# main.net
KiCad netlist of a schematic drawn in Altium Designer
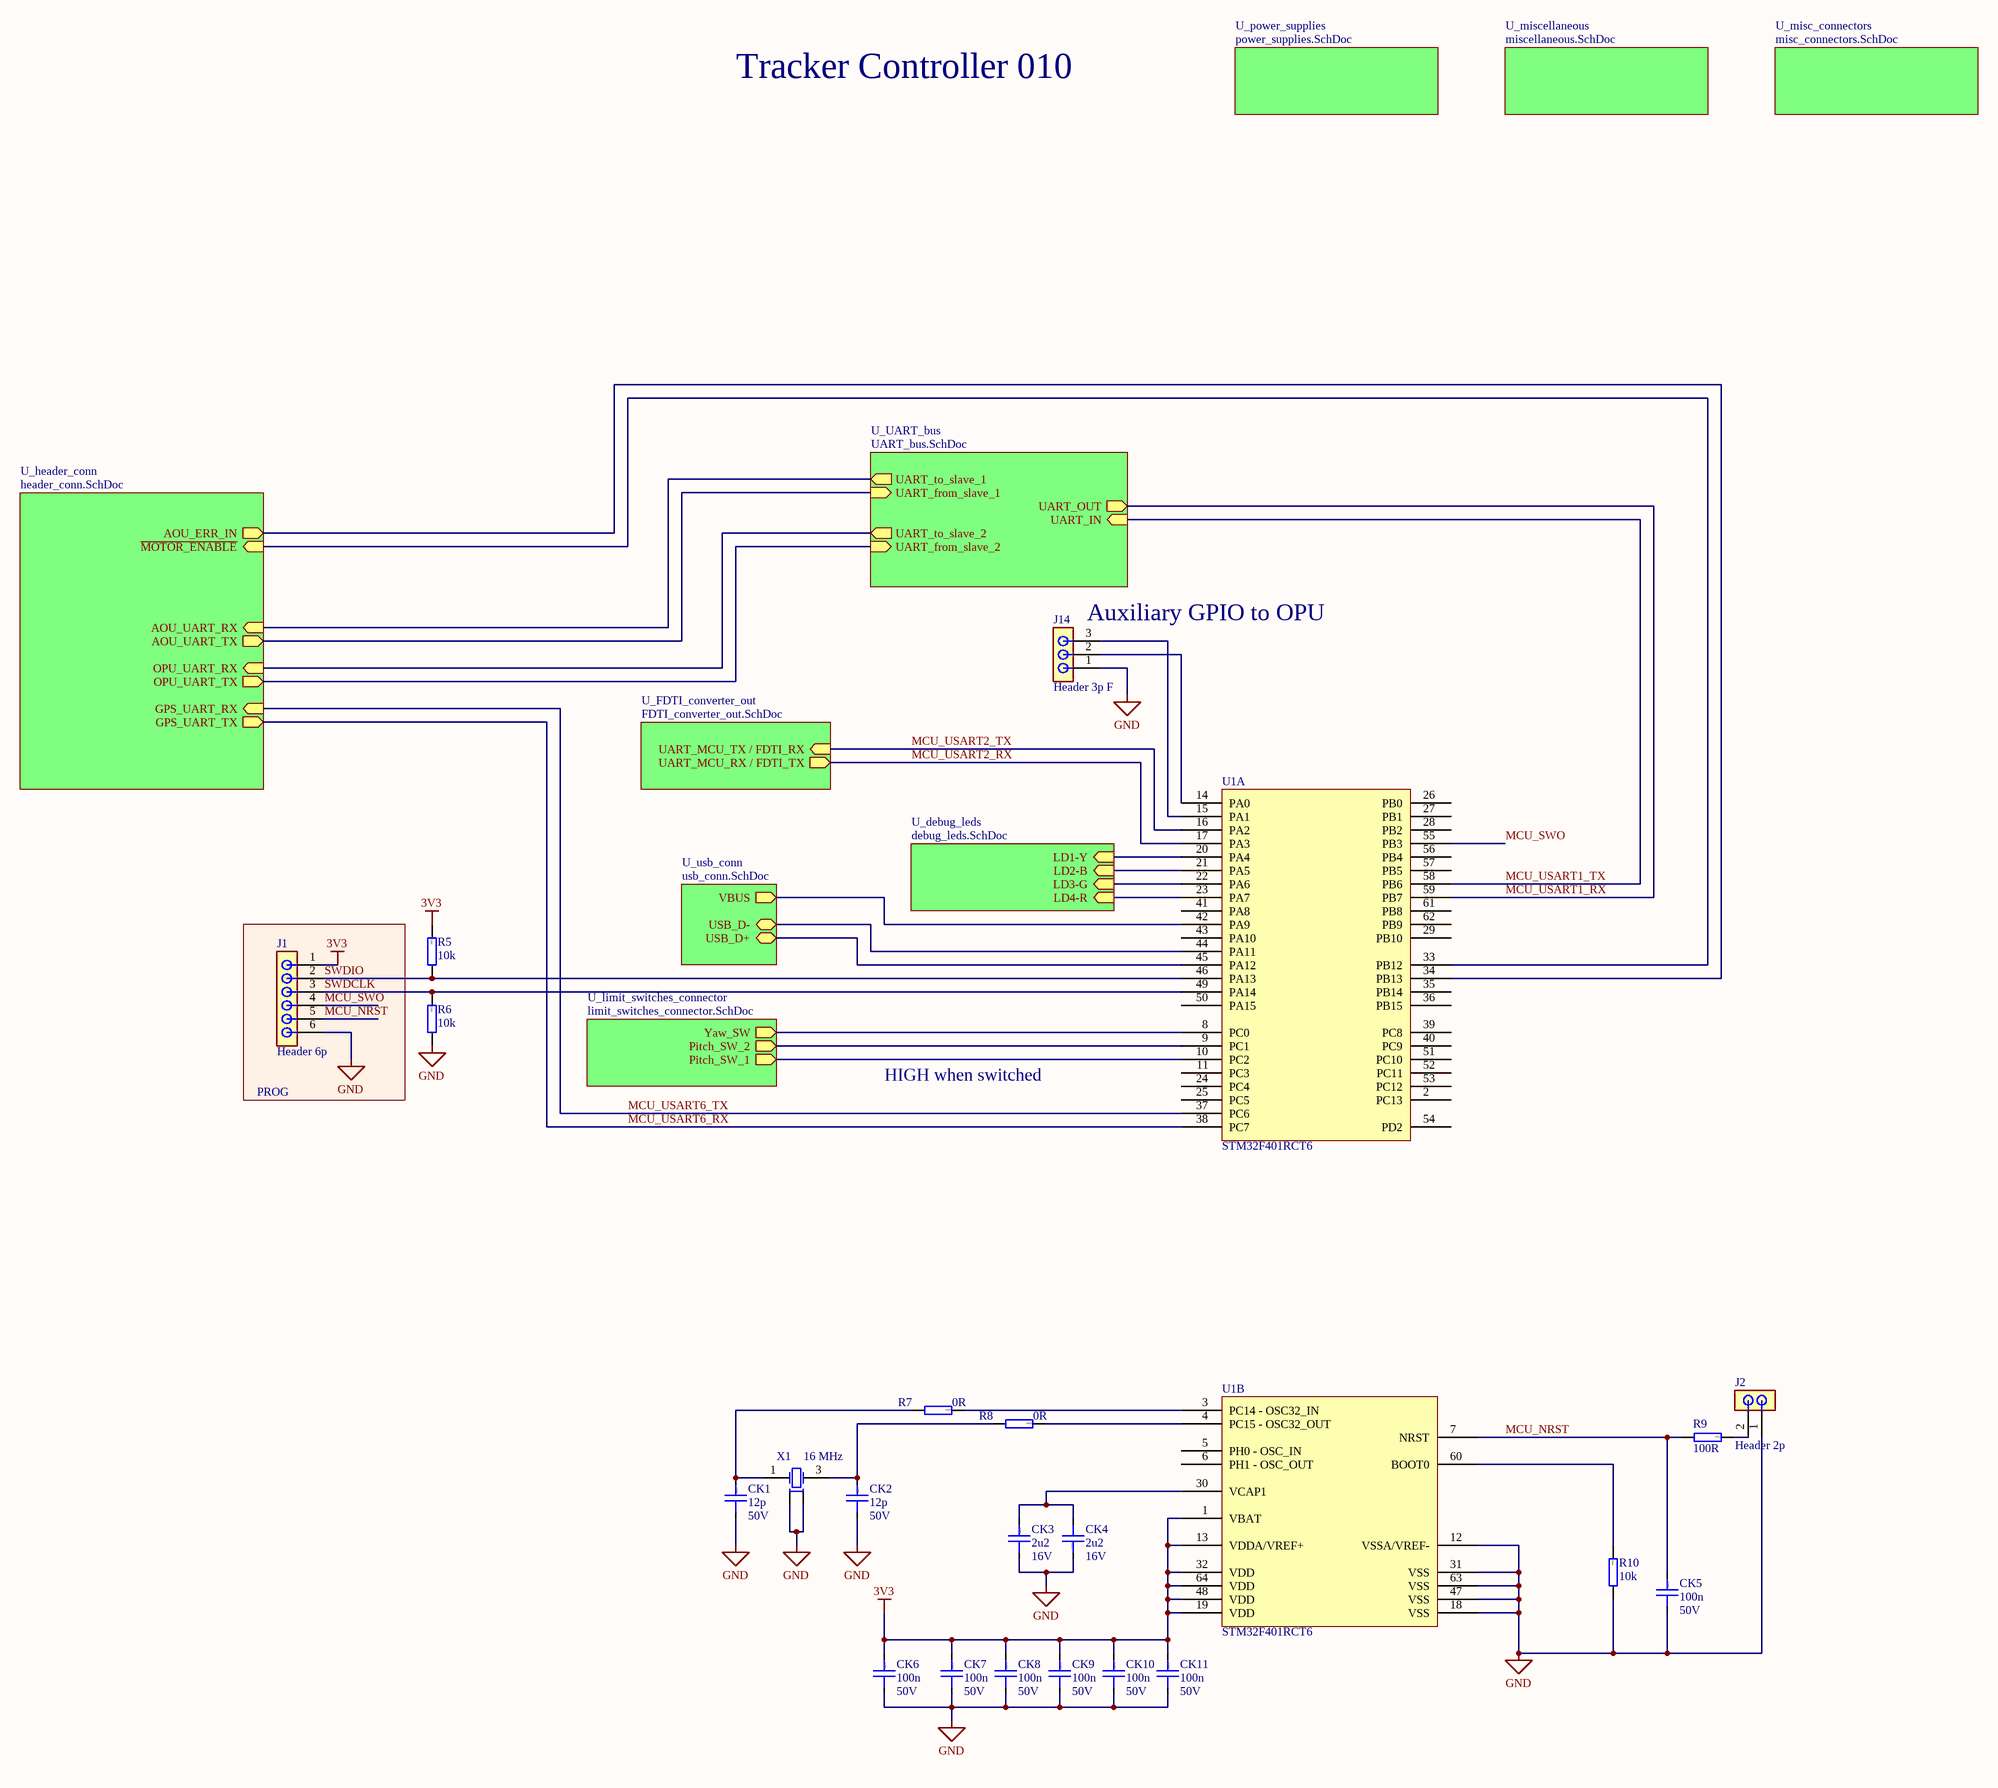
[diagram p0: main.SchDoc]

(export (version "E")
  (design (tool "Eeschema 10.0.6"))
  (components
    (comp (ref "CK1")
      (value "12p")
      (footprint "CAP0603")
      (description "50V 12pF C0G ±5% 0603 Multilayer Ceramic Capacitors MLCC - SMD/SMT ROHS")
      (fields (field (name "JLCPCB PART") "C38523") (field (name "VOLTAGE RATING") "50V"))
      (libsource (lib "Kubikova ultra knihovna") (part "Cap 12p 0603"))
    )
    (comp (ref "CK2")
      (value "12p")
      (footprint "CAP0603")
      (description "50V 12pF C0G ±5% 0603 Multilayer Ceramic Capacitors MLCC - SMD/SMT ROHS")
      (fields (field (name "JLCPCB PART") "C38523") (field (name "VOLTAGE RATING") "50V"))
      (libsource (lib "Kubikova ultra knihovna") (part "Cap 12p 0603"))
    )
    (comp (ref "CK3")
      (value "2u2")
      (footprint "CAP0603")
      (description "16V 2.2uF X5R ±10% 0603 Multilayer Ceramic Capacitors MLCC - SMD/SMT ROHS")
      (fields (field (name "JLCPCB PART") "C23630") (field (name "VOLTAGE RATING") "16V"))
      (libsource (lib "Kubikova ultra knihovna") (part "Cap 2u2 0603"))
    )
    (comp (ref "CK4")
      (value "2u2")
      (footprint "CAP0603")
      (description "16V 2.2uF X5R ±10% 0603 Multilayer Ceramic Capacitors MLCC - SMD/SMT ROHS")
      (fields (field (name "JLCPCB PART") "C23630") (field (name "VOLTAGE RATING") "16V"))
      (libsource (lib "Kubikova ultra knihovna") (part "Cap 2u2 0603"))
    )
    (comp (ref "CK5")
      (value "100n")
      (footprint "CAP0603")
      (description "50V 100nF X7R ±10% 0603 Multilayer Ceramic Capacitors MLCC - SMD/SMT ROHS")
      (fields (field (name "JLCPCB PART") "C14663") (field (name "VOLTAGE RATING") "50V"))
      (libsource (lib "Kubikova ultra knihovna") (part "Cap 100n 0603"))
    )
    (comp (ref "CK6")
      (value "100n")
      (footprint "CAP0603")
      (description "50V 100nF X7R ±10% 0603 Multilayer Ceramic Capacitors MLCC - SMD/SMT ROHS")
      (fields (field (name "JLCPCB PART") "C14663") (field (name "VOLTAGE RATING") "50V"))
      (libsource (lib "Kubikova ultra knihovna") (part "Cap 100n 0603"))
    )
    (comp (ref "CK7")
      (value "100n")
      (footprint "CAP0603")
      (description "50V 100nF X7R ±10% 0603 Multilayer Ceramic Capacitors MLCC - SMD/SMT ROHS")
      (fields (field (name "JLCPCB PART") "C14663") (field (name "VOLTAGE RATING") "50V"))
      (libsource (lib "Kubikova ultra knihovna") (part "Cap 100n 0603"))
    )
    (comp (ref "CK8")
      (value "100n")
      (footprint "CAP0603")
      (description "50V 100nF X7R ±10% 0603 Multilayer Ceramic Capacitors MLCC - SMD/SMT ROHS")
      (fields (field (name "JLCPCB PART") "C14663") (field (name "VOLTAGE RATING") "50V"))
      (libsource (lib "Kubikova ultra knihovna") (part "Cap 100n 0603"))
    )
    (comp (ref "CK9")
      (value "100n")
      (footprint "CAP0603")
      (description "50V 100nF X7R ±10% 0603 Multilayer Ceramic Capacitors MLCC - SMD/SMT ROHS")
      (fields (field (name "JLCPCB PART") "C14663") (field (name "VOLTAGE RATING") "50V"))
      (libsource (lib "Kubikova ultra knihovna") (part "Cap 100n 0603"))
    )
    (comp (ref "CK10")
      (value "100n")
      (footprint "CAP0603")
      (description "50V 100nF X7R ±10% 0603 Multilayer Ceramic Capacitors MLCC - SMD/SMT ROHS")
      (fields (field (name "JLCPCB PART") "C14663") (field (name "VOLTAGE RATING") "50V"))
      (libsource (lib "Kubikova ultra knihovna") (part "Cap 100n 0603"))
    )
    (comp (ref "CK11")
      (value "100n")
      (footprint "CAP0603")
      (description "50V 100nF X7R ±10% 0603 Multilayer Ceramic Capacitors MLCC - SMD/SMT ROHS")
      (fields (field (name "JLCPCB PART") "C14663") (field (name "VOLTAGE RATING") "50V"))
      (libsource (lib "Kubikova ultra knihovna") (part "Cap 100n 0603"))
    )
    (comp (ref "J1")
      (value "Header 6p")
      (footprint "Pin header 6p")
      (fields
        (field (name "MANUFACTURER_PART_NUMBER") "DS1021-1*2SF11-B")
        (field (name "JLCPCB PART") "C37208")
      )
      (libsource (lib "Kubikova ultra knihovna") (part "Pin header 6p"))
    )
    (comp (ref "J2")
      (value "Header 2p")
      (footprint "Pin header 2p")
      (description "Connector")
      (fields
        (field (name "MANUFACTURER_PART_NUMBER") "DS1021-1*2SF11-B")
        (field (name "JLCPCB PART") "C492401")
      )
      (libsource (lib "Kubikova ultra knihovna") (part "Pin header 2p"))
    )
    (comp (ref "J14")
      (value "Header 3p F")
      (footprint "Pin header 3p - F")
      (description "Direct Insert 2.54mm Policy 3A 2.5mm -40℃~+105℃ 3mm 6mm 250V Black 1x3P Single Row 3P Pin Headers")
      (fields (field (name "MANUFACTURER_PART_NUMBER") "DS1021-1*2SF11-B"))
      (libsource (lib "Kubikova ultra knihovna") (part "Pin header 3p_F"))
    )
    (comp (ref "R5")
      (value "10k")
      (footprint "RESC2012X06N(SMR0805)")
      (description "125mW Thick Film Resistors 150V ±100ppm/℃ ±1% 10kΩ 0805 Chip Resistor - Surface Mount ROHS")
      (fields (field (name "JLCPCB PART") "C17414"))
      (libsource (lib "Kubikova ultra knihovna") (part "Res 10k 0805"))
    )
    (comp (ref "R6")
      (value "10k")
      (footprint "RESC2012X06N(SMR0805)")
      (description "125mW Thick Film Resistors 150V ±100ppm/℃ ±1% 10kΩ 0805 Chip Resistor - Surface Mount ROHS")
      (fields (field (name "JLCPCB PART") "C17414"))
      (libsource (lib "Kubikova ultra knihovna") (part "Res 10k 0805"))
    )
    (comp (ref "R7")
      (value "0R")
      (footprint "RESC2012X06N(SMR0805)")
      (description "125mW Thick Film Resistors 150V ±800ppm/℃ ±1% 0Ω 0805 Chip Resistor - Surface Mount ROHS")
      (fields (field (name "JLCPCB PART") "C17477") (field (name "AUTHOR") "JP/27.03.2014"))
      (libsource (lib "Kubikova ultra knihovna") (part "Res 0R 0805"))
    )
    (comp (ref "R8")
      (value "0R")
      (footprint "RESC2012X06N(SMR0805)")
      (description "125mW Thick Film Resistors 150V ±800ppm/℃ ±1% 0Ω 0805 Chip Resistor - Surface Mount ROHS")
      (fields (field (name "JLCPCB PART") "C17477") (field (name "AUTHOR") "JP/27.03.2014"))
      (libsource (lib "Kubikova ultra knihovna") (part "Res 0R 0805"))
    )
    (comp (ref "R9")
      (value "100R")
      (footprint "RESC2012X06N(SMR0805)")
      (description "125mW Thick Film Resistors 150V ±100ppm/℃ ±1% 100Ω 0805 Chip Resistor - Surface Mount ROHS")
      (fields (field (name "JLCPCB PART") "C17408") (field (name "AUTHOR") "JP/27.03.2014"))
      (libsource (lib "Kubikova ultra knihovna") (part "Res 100R 0805"))
    )
    (comp (ref "R10")
      (value "10k")
      (footprint "RESC2012X06N(SMR0805)")
      (description "125mW Thick Film Resistors 150V ±100ppm/℃ ±1% 10kΩ 0805 Chip Resistor - Surface Mount ROHS")
      (fields (field (name "JLCPCB PART") "C17414"))
      (libsource (lib "Kubikova ultra knihovna") (part "Res 10k 0805"))
    )
    (comp (ref "U1")
      (value "STM32F401RCT6")
      (footprint "LQFP64")
      (description "256KB 1.7V~3.6V ARM-M4 64KB 84MHz FLASH 50 LQFP-64(10x10) Microcontrollers (MCU/MPU/SOC) ROHS")
      (fields (field (name "JLCPCB PART") "C74524"))
      (libsource (lib "Kubikova ultra knihovna") (part "STM32F401RCT6"))
    )
    (comp (ref "X1")
      (value "16 MHz")
      (footprint "3225 XTal")
      (description "X322516MLB4SI\r\n16MHz Surface Mount Crystal 9pF ±10ppm ±20ppm SMD3225-4P Crystals ROHS")
      (libsource (lib "Kubikova ultra knihovna") (part "16 MHz crystal"))
    )
  )
  (nets
    (net (code "1") (name "/AOU_ERR_IN") (class "Default")
      (node (ref "U1") (pin "34") (pinfunction "PB13_34") (pintype "passive"))
    )
    (net (code "3") (name "/LD1-Y") (class "Default")
      (node (ref "U1") (pin "20") (pinfunction "PA4_20") (pintype "passive"))
    )
    (net (code "4") (name "/LD2-B") (class "Default")
      (node (ref "U1") (pin "21") (pinfunction "PA5_21") (pintype "passive"))
    )
    (net (code "5") (name "/LD3-G") (class "Default")
      (node (ref "U1") (pin "22") (pinfunction "PA6_22") (pintype "passive"))
    )
    (net (code "6") (name "/LD4-R") (class "Default")
      (node (ref "U1") (pin "23") (pinfunction "PA7_23") (pintype "passive"))
    )
    (net (code "7") (name "/MCU_NRST") (class "Default")
      (node (ref "CK5") (pin "1") (pinfunction "1_1") (pintype "passive"))
      (node (ref "J1") (pin "5") (pinfunction "5_5") (pintype "passive"))
      (node (ref "R9") (pin "1") (pinfunction "1_1") (pintype "passive"))
      (node (ref "U1") (pin "7") (pinfunction "NRST_7") (pintype "passive"))
    )
    (net (code "8") (name "/MCU_SWO") (class "Default")
      (node (ref "J1") (pin "4") (pinfunction "4_4") (pintype "passive"))
      (node (ref "U1") (pin "55") (pinfunction "PB3_55") (pintype "passive"))
    )
    (net (code "9") (name "/MCU_USART1_RX") (class "Default")
      (node (ref "U1") (pin "59") (pinfunction "PB7_59") (pintype "passive"))
    )
    (net (code "10") (name "/MCU_USART1_TX") (class "Default")
      (node (ref "U1") (pin "58") (pinfunction "PB6_58") (pintype "passive"))
    )
    (net (code "11") (name "/MCU_USART2_RX") (class "Default")
      (node (ref "U1") (pin "17") (pinfunction "PA3_17") (pintype "passive"))
    )
    (net (code "12") (name "/MCU_USART2_TX") (class "Default")
      (node (ref "U1") (pin "16") (pinfunction "PA2_16") (pintype "passive"))
    )
    (net (code "13") (name "/MCU_USART6_RX") (class "Default")
      (node (ref "U1") (pin "38") (pinfunction "PC7_38") (pintype "passive"))
    )
    (net (code "14") (name "/MCU_USART6_TX") (class "Default")
      (node (ref "U1") (pin "37") (pinfunction "PC6_37") (pintype "passive"))
    )
    (net (code "16") (name "/Pitch_SW_1") (class "Default")
      (node (ref "U1") (pin "10") (pinfunction "PC2_10") (pintype "passive"))
    )
    (net (code "17") (name "/Pitch_SW_2") (class "Default")
      (node (ref "U1") (pin "9") (pinfunction "PC1_9") (pintype "passive"))
    )
    (net (code "18") (name "/SWDCLK") (class "Default")
      (node (ref "J1") (pin "3") (pinfunction "3_3") (pintype "passive"))
      (node (ref "R6") (pin "2") (pinfunction "2_2") (pintype "passive"))
      (node (ref "U1") (pin "49") (pinfunction "PA14_49") (pintype "passive"))
    )
    (net (code "19") (name "/SWDIO") (class "Default")
      (node (ref "J1") (pin "2") (pinfunction "2_2") (pintype "passive"))
      (node (ref "R5") (pin "1") (pinfunction "1_1") (pintype "passive"))
      (node (ref "U1") (pin "46") (pinfunction "PA13_46") (pintype "passive"))
    )
    (net (code "22") (name "/USB_D+") (class "Default")
      (node (ref "U1") (pin "45") (pinfunction "PA12_45") (pintype "passive"))
    )
    (net (code "23") (name "/USB_D-") (class "Default")
      (node (ref "U1") (pin "44") (pinfunction "PA11_44") (pintype "passive"))
    )
    (net (code "24") (name "/VBUS") (class "Default")
      (node (ref "U1") (pin "42") (pinfunction "PA9_42") (pintype "passive"))
    )
    (net (code "25") (name "/Yaw_SW") (class "Default")
      (node (ref "U1") (pin "8") (pinfunction "PC0_8") (pintype "passive"))
    )
    (net (code "26") (name "/~{MOTOR_ENABLE}") (class "Default")
      (node (ref "U1") (pin "33") (pinfunction "PB12_33") (pintype "passive"))
    )
    (net (code "27") (name "3V3") (class "Default")
      (node (ref "CK10") (pin "1") (pinfunction "1_1") (pintype "passive"))
      (node (ref "CK11") (pin "1") (pinfunction "1_1") (pintype "passive"))
      (node (ref "CK6") (pin "1") (pinfunction "1_1") (pintype "passive"))
      (node (ref "CK7") (pin "1") (pinfunction "1_1") (pintype "passive"))
      (node (ref "CK8") (pin "1") (pinfunction "1_1") (pintype "passive"))
      (node (ref "CK9") (pin "1") (pinfunction "1_1") (pintype "passive"))
      (node (ref "J1") (pin "1") (pinfunction "1_1") (pintype "passive"))
      (node (ref "R5") (pin "2") (pinfunction "2_2") (pintype "passive"))
      (node (ref "U1") (pin "1") (pinfunction "VBAT_1") (pintype "passive"))
      (node (ref "U1") (pin "13") (pinfunction "VDDA/VREF+_13") (pintype "passive"))
      (node (ref "U1") (pin "19") (pinfunction "VDD_19") (pintype "passive"))
      (node (ref "U1") (pin "32") (pinfunction "VDD_32") (pintype "passive"))
      (node (ref "U1") (pin "48") (pinfunction "VDD_48") (pintype "passive"))
      (node (ref "U1") (pin "64") (pinfunction "VDD_64") (pintype "passive"))
    )
    (net (code "28") (name "GND") (class "Default")
      (node (ref "CK1") (pin "2") (pinfunction "2_2") (pintype "passive"))
      (node (ref "CK10") (pin "2") (pinfunction "2_2") (pintype "passive"))
      (node (ref "CK11") (pin "2") (pinfunction "2_2") (pintype "passive"))
      (node (ref "CK2") (pin "2") (pinfunction "2_2") (pintype "passive"))
      (node (ref "CK3") (pin "2") (pinfunction "2_2") (pintype "passive"))
      (node (ref "CK4") (pin "1") (pinfunction "1_1") (pintype "passive"))
      (node (ref "CK5") (pin "2") (pinfunction "2_2") (pintype "passive"))
      (node (ref "CK6") (pin "2") (pinfunction "2_2") (pintype "passive"))
      (node (ref "CK7") (pin "2") (pinfunction "2_2") (pintype "passive"))
      (node (ref "CK8") (pin "2") (pinfunction "2_2") (pintype "passive"))
      (node (ref "CK9") (pin "2") (pinfunction "2_2") (pintype "passive"))
      (node (ref "J1") (pin "6") (pinfunction "6_6") (pintype "passive"))
      (node (ref "J14") (pin "1") (pinfunction "1_1") (pintype "passive"))
      (node (ref "J2") (pin "1") (pinfunction "1_1") (pintype "passive"))
      (node (ref "R10") (pin "1") (pinfunction "1_1") (pintype "passive"))
      (node (ref "R6") (pin "1") (pinfunction "1_1") (pintype "passive"))
      (node (ref "U1") (pin "12") (pinfunction "VSSA/VREF-_12") (pintype "passive"))
      (node (ref "U1") (pin "18") (pinfunction "VSS_18") (pintype "passive"))
      (node (ref "U1") (pin "31") (pinfunction "VSS_31") (pintype "passive"))
      (node (ref "U1") (pin "47") (pinfunction "VSS_47") (pintype "passive"))
      (node (ref "U1") (pin "63") (pinfunction "VSS_63") (pintype "passive"))
      (node (ref "X1") (pin "2") (pinfunction "2_2") (pintype "passive"))
      (node (ref "X1") (pin "4") (pinfunction "4_4") (pintype "passive"))
    )
    (net (code "29") (name "Net-(CK1-Pad1)") (class "Default")
      (node (ref "CK1") (pin "1") (pinfunction "1_1") (pintype "passive"))
      (node (ref "R7") (pin "1") (pinfunction "1_1") (pintype "passive"))
      (node (ref "X1") (pin "1") (pinfunction "1_1") (pintype "passive"))
    )
    (net (code "30") (name "Net-(CK2-Pad1)") (class "Default")
      (node (ref "CK2") (pin "1") (pinfunction "1_1") (pintype "passive"))
      (node (ref "R8") (pin "1") (pinfunction "1_1") (pintype "passive"))
      (node (ref "X1") (pin "3") (pinfunction "3_3") (pintype "passive"))
    )
    (net (code "31") (name "Net-(J2-Pad2)") (class "Default")
      (node (ref "J2") (pin "2") (pinfunction "2_2") (pintype "passive"))
      (node (ref "R9") (pin "2") (pinfunction "2_2") (pintype "passive"))
    )
    (net (code "32") (name "Net-(U1A-PA0)") (class "Default")
      (node (ref "J14") (pin "2") (pinfunction "2_2") (pintype "passive"))
      (node (ref "U1") (pin "14") (pinfunction "PA0_14") (pintype "passive"))
    )
    (net (code "33") (name "Net-(U1A-PA1)") (class "Default")
      (node (ref "J14") (pin "3") (pinfunction "3_3") (pintype "passive"))
      (node (ref "U1") (pin "15") (pinfunction "PA1_15") (pintype "passive"))
    )
    (net (code "34") (name "Net-(U1B-BOOT0)") (class "Default")
      (node (ref "R10") (pin "2") (pinfunction "2_2") (pintype "passive"))
      (node (ref "U1") (pin "60") (pinfunction "BOOT0_60") (pintype "passive"))
    )
    (net (code "35") (name "Net-(U1B-PC14_-_OSC32_IN)") (class "Default")
      (node (ref "R7") (pin "2") (pinfunction "2_2") (pintype "passive"))
      (node (ref "U1") (pin "3") (pinfunction "PC14_-_OSC32_IN_3") (pintype "passive"))
    )
    (net (code "36") (name "Net-(U1B-PC15_-_OSC32_OUT)") (class "Default")
      (node (ref "R8") (pin "2") (pinfunction "2_2") (pintype "passive"))
      (node (ref "U1") (pin "4") (pinfunction "PC15_-_OSC32_OUT_4") (pintype "passive"))
    )
    (net (code "37") (name "Net-(U1B-VCAP1)") (class "Default")
      (node (ref "CK3") (pin "1") (pinfunction "1_1") (pintype "passive"))
      (node (ref "CK4") (pin "2") (pinfunction "2_2") (pintype "passive"))
      (node (ref "U1") (pin "30") (pinfunction "VCAP1_30") (pintype "passive"))
    )
    (net (code "38") (name "unconnected-(U1A-PA8-Pad41)") (class "Default")
      (node (ref "U1") (pin "41") (pinfunction "PA8_41") (pintype "passive"))
    )
    (net (code "39") (name "unconnected-(U1A-PA10-Pad43)") (class "Default")
      (node (ref "U1") (pin "43") (pinfunction "PA10_43") (pintype "passive"))
    )
    (net (code "40") (name "unconnected-(U1A-PA15-Pad50)") (class "Default")
      (node (ref "U1") (pin "50") (pinfunction "PA15_50") (pintype "passive"))
    )
    (net (code "41") (name "unconnected-(U1A-PB0-Pad26)") (class "Default")
      (node (ref "U1") (pin "26") (pinfunction "PB0_26") (pintype "passive"))
    )
    (net (code "42") (name "unconnected-(U1A-PB1-Pad27)") (class "Default")
      (node (ref "U1") (pin "27") (pinfunction "PB1_27") (pintype "passive"))
    )
    (net (code "43") (name "unconnected-(U1A-PB2-Pad28)") (class "Default")
      (node (ref "U1") (pin "28") (pinfunction "PB2_28") (pintype "passive"))
    )
    (net (code "44") (name "unconnected-(U1A-PB4-Pad56)") (class "Default")
      (node (ref "U1") (pin "56") (pinfunction "PB4_56") (pintype "passive"))
    )
    (net (code "45") (name "unconnected-(U1A-PB5-Pad57)") (class "Default")
      (node (ref "U1") (pin "57") (pinfunction "PB5_57") (pintype "passive"))
    )
    (net (code "46") (name "unconnected-(U1A-PB8-Pad61)") (class "Default")
      (node (ref "U1") (pin "61") (pinfunction "PB8_61") (pintype "passive"))
    )
    (net (code "47") (name "unconnected-(U1A-PB9-Pad62)") (class "Default")
      (node (ref "U1") (pin "62") (pinfunction "PB9_62") (pintype "passive"))
    )
    (net (code "48") (name "unconnected-(U1A-PB10-Pad29)") (class "Default")
      (node (ref "U1") (pin "29") (pinfunction "PB10_29") (pintype "passive"))
    )
    (net (code "49") (name "unconnected-(U1A-PB14-Pad35)") (class "Default")
      (node (ref "U1") (pin "35") (pinfunction "PB14_35") (pintype "passive"))
    )
    (net (code "50") (name "unconnected-(U1A-PB15-Pad36)") (class "Default")
      (node (ref "U1") (pin "36") (pinfunction "PB15_36") (pintype "passive"))
    )
    (net (code "51") (name "unconnected-(U1A-PC3-Pad11)") (class "Default")
      (node (ref "U1") (pin "11") (pinfunction "PC3_11") (pintype "passive"))
    )
    (net (code "52") (name "unconnected-(U1A-PC4-Pad24)") (class "Default")
      (node (ref "U1") (pin "24") (pinfunction "PC4_24") (pintype "passive"))
    )
    (net (code "53") (name "unconnected-(U1A-PC5-Pad25)") (class "Default")
      (node (ref "U1") (pin "25") (pinfunction "PC5_25") (pintype "passive"))
    )
    (net (code "54") (name "unconnected-(U1A-PC8-Pad39)") (class "Default")
      (node (ref "U1") (pin "39") (pinfunction "PC8_39") (pintype "passive"))
    )
    (net (code "55") (name "unconnected-(U1A-PC9-Pad40)") (class "Default")
      (node (ref "U1") (pin "40") (pinfunction "PC9_40") (pintype "passive"))
    )
    (net (code "56") (name "unconnected-(U1A-PC10-Pad51)") (class "Default")
      (node (ref "U1") (pin "51") (pinfunction "PC10_51") (pintype "passive"))
    )
    (net (code "57") (name "unconnected-(U1A-PC11-Pad52)") (class "Default")
      (node (ref "U1") (pin "52") (pinfunction "PC11_52") (pintype "passive"))
    )
    (net (code "58") (name "unconnected-(U1A-PC12-Pad53)") (class "Default")
      (node (ref "U1") (pin "53") (pinfunction "PC12_53") (pintype "passive"))
    )
    (net (code "59") (name "unconnected-(U1A-PC13-Pad2)") (class "Default")
      (node (ref "U1") (pin "2") (pinfunction "PC13_2") (pintype "passive"))
    )
    (net (code "60") (name "unconnected-(U1A-PD2-Pad54)") (class "Default")
      (node (ref "U1") (pin "54") (pinfunction "PD2_54") (pintype "passive"))
    )
    (net (code "61") (name "unconnected-(U1B-PH0_-_OSC_IN-Pad5)") (class "Default")
      (node (ref "U1") (pin "5") (pinfunction "PH0_-_OSC_IN_5") (pintype "passive"))
    )
    (net (code "62") (name "unconnected-(U1B-PH1_-_OSC_OUT-Pad6)") (class "Default")
      (node (ref "U1") (pin "6") (pinfunction "PH1_-_OSC_OUT_6") (pintype "passive"))
    )
  )
)
